# tick-wifi-mk-1_1a.net
KiCad netlist of a schematic drawn in EAGLE
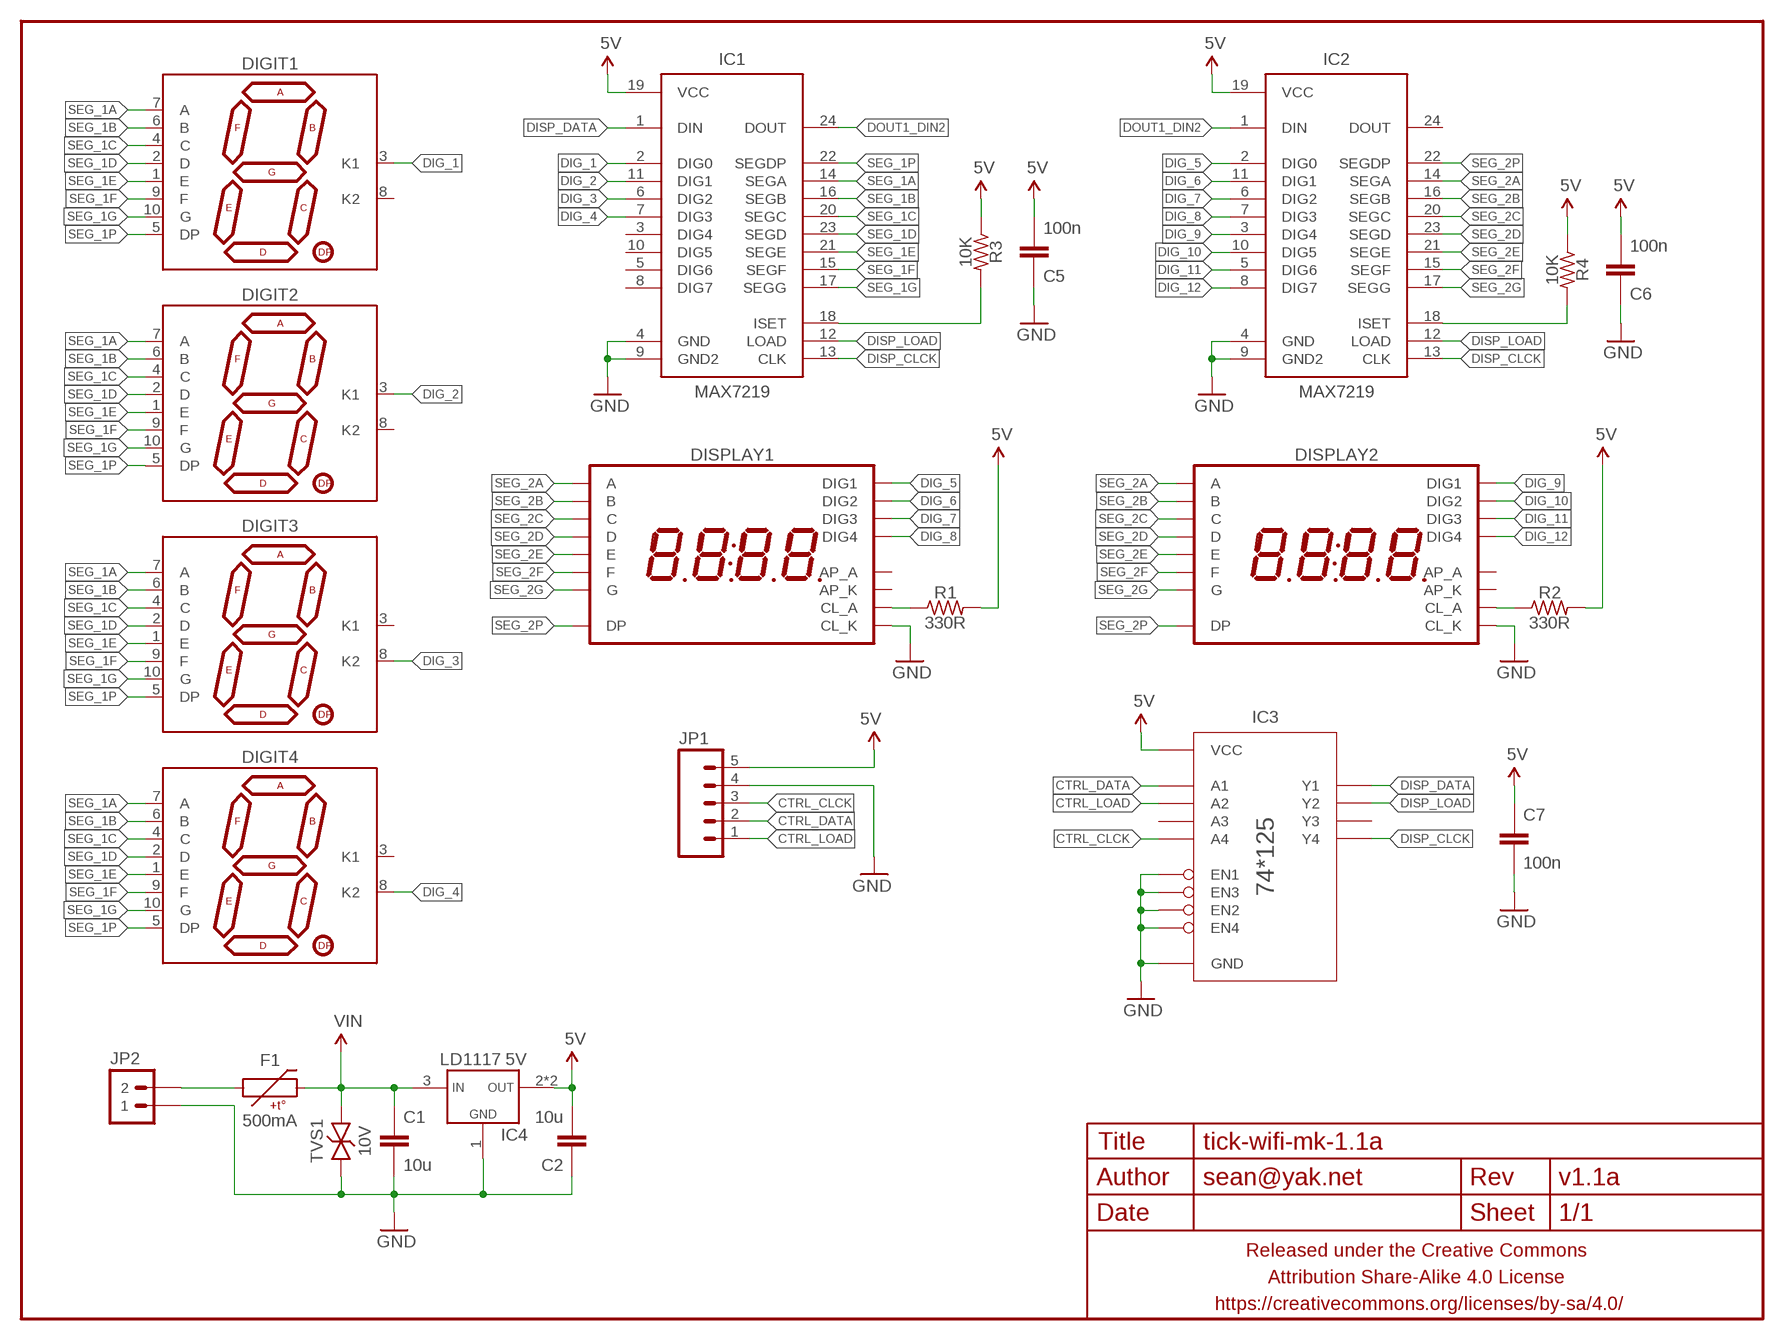
[diagram p0: schematic, sheet 1]

(export (version "E")
  (design (tool "Eeschema 10.0.6"))
  (components
    (comp (ref "C1")
      (value "10u")
      (footprint "eagle-import:C1210")
      (libsource (lib "eagle-import") (part "CAPACITOR-CERAMICC1210"))
    )
    (comp (ref "C2")
      (value "10u")
      (footprint "eagle-import:C1210")
      (libsource (lib "eagle-import") (part "CAPACITOR-CERAMICC1210"))
    )
    (comp (ref "C5")
      (value "100n")
      (footprint "eagle-import:C0603")
      (libsource (lib "eagle-import") (part "CAPACITOR-CERAMICC0603"))
    )
    (comp (ref "C6")
      (value "100n")
      (footprint "eagle-import:C0603")
      (libsource (lib "eagle-import") (part "CAPACITOR-CERAMICC0603"))
    )
    (comp (ref "C7")
      (value "100n")
      (footprint "eagle-import:C0603")
      (libsource (lib "eagle-import") (part "CAPACITOR-CERAMICC0603"))
    )
    (comp (ref "DIGIT1")
      (value "7SEG_1DIGPTH-25.4MM-BARE")
      (footprint "eagle-import:7SEG_1DIG_25.4MM_NOSILK")
      (libsource (lib "eagle-import") (part "7SEG_1DIGPTH-25.4MM-BARE"))
    )
    (comp (ref "DIGIT2")
      (value "7SEG_1DIGPTH-25.4MM-BARE")
      (footprint "eagle-import:7SEG_1DIG_25.4MM_NOSILK")
      (libsource (lib "eagle-import") (part "7SEG_1DIGPTH-25.4MM-BARE"))
    )
    (comp (ref "DIGIT3")
      (value "7SEG_1DIGPTH-25.4MM-BARE")
      (footprint "eagle-import:7SEG_1DIG_25.4MM_NOSILK")
      (libsource (lib "eagle-import") (part "7SEG_1DIGPTH-25.4MM-BARE"))
    )
    (comp (ref "DIGIT4")
      (value "7SEG_1DIGPTH-25.4MM-BARE")
      (footprint "eagle-import:7SEG_1DIG_25.4MM_NOSILK")
      (libsource (lib "eagle-import") (part "7SEG_1DIGPTH-25.4MM-BARE"))
    )
    (comp (ref "DISPLAY1")
      (value "7SEG_4DIGIT_COLON_APOS")
      (footprint "eagle-import:7SEG_4DIG_10MM")
      (libsource (lib "eagle-import") (part "7SEG_4DIGIT_COLON_APOS"))
    )
    (comp (ref "DISPLAY2")
      (value "7SEG_4DIGIT_COLON_APOS")
      (footprint "eagle-import:7SEG_4DIG_10MM")
      (libsource (lib "eagle-import") (part "7SEG_4DIGIT_COLON_APOS"))
    )
    (comp (ref "F1")
      (value "500mA")
      (footprint "eagle-import:PTC-1210")
      (libsource (lib "eagle-import") (part "PTCPTC-1210"))
    )
    (comp (ref "FRAME1")
      (value "FRAME-LETTERNO_PACKAGE")
      (footprint "eagle-import:DUMMY")
      (fields (field (name "DESIGNER") "sean@yak.net") (field (name "VERSION") "v1.1a"))
      (libsource (lib "eagle-import") (part "FRAME-LETTERNO_PACKAGE"))
    )
    (comp (ref "IC1")
      (value "MAX7219")
      (footprint "eagle-import:SO24W")
      (libsource (lib "eagle-import") (part "MAX7219SOIC-W"))
    )
    (comp (ref "IC2")
      (value "MAX7219")
      (footprint "eagle-import:SO24W")
      (libsource (lib "eagle-import") (part "MAX7219SOIC-W"))
    )
    (comp (ref "IC3")
      (value "74HC125")
      (footprint "eagle-import:SO14")
      (libsource (lib "eagle-import") (part "74125SOIC14"))
    )
    (comp (ref "IC4")
      (value "LD1117 5V")
      (footprint "eagle-import:SOT223")
      (libsource (lib "eagle-import") (part "VREG_1117SOT223"))
    )
    (comp (ref "JP1")
      (value "M05PTH-CENTERED")
      (footprint "eagle-import:1X05_PTH_CENTERED")
      (libsource (lib "eagle-import") (part "M05PTH-CENTERED"))
    )
    (comp (ref "JP2")
      (value "M02PTH-CENTERED-R+")
      (footprint "eagle-import:1X02-CENTER-R+")
      (libsource (lib "eagle-import") (part "M02PTH-CENTERED-R+"))
    )
    (comp (ref "R1")
      (value "330R")
      (footprint "eagle-import:R0603")
      (libsource (lib "eagle-import") (part "RESISTORR0603"))
    )
    (comp (ref "R2")
      (value "330R")
      (footprint "eagle-import:R0603")
      (libsource (lib "eagle-import") (part "RESISTORR0603"))
    )
    (comp (ref "R3")
      (value "10K")
      (footprint "eagle-import:R0603")
      (libsource (lib "eagle-import") (part "RESISTORR0603"))
    )
    (comp (ref "R4")
      (value "10K")
      (footprint "eagle-import:R0603")
      (libsource (lib "eagle-import") (part "RESISTORR0603"))
    )
    (comp (ref "TVS1")
      (value "10V")
      (footprint "eagle-import:SMA-DIODE-TVS-BIDIR")
      (libsource (lib "eagle-import") (part "TVSSMA"))
    )
  )
  (nets
    (net (code "1") (name "5V") (class "Default")
      (node (ref "C2") (pin "2") (pinfunction "2_2") (pintype "passive"))
      (node (ref "C5") (pin "2") (pinfunction "2_2") (pintype "passive"))
      (node (ref "C6") (pin "2") (pinfunction "2_2") (pintype "passive"))
      (node (ref "C7") (pin "1") (pinfunction "1_1") (pintype "passive"))
      (node (ref "IC1") (pin "19") (pinfunction "VCC_19") (pintype "bidirectional"))
      (node (ref "IC2") (pin "19") (pinfunction "VCC_19") (pintype "bidirectional"))
      (node (ref "IC3") (pin "14") (pinfunction "VCC_14") (pintype "bidirectional"))
      (node (ref "IC4") (pin "2") (pinfunction "VOUT_2") (pintype "bidirectional"))
      (node (ref "IC4") (pin "4") (pinfunction "VOUT_4") (pintype "bidirectional"))
      (node (ref "JP1") (pin "5") (pinfunction "5_5") (pintype "passive"))
      (node (ref "R1") (pin "2") (pinfunction "2_2") (pintype "passive"))
      (node (ref "R2") (pin "2") (pinfunction "2_2") (pintype "passive"))
      (node (ref "R3") (pin "1") (pinfunction "1_1") (pintype "passive"))
      (node (ref "R4") (pin "1") (pinfunction "1_1") (pintype "passive"))
    )
    (net (code "2") (name "CTRL_CLCK") (class "Default")
      (node (ref "IC3") (pin "12") (pinfunction "A4_12") (pintype "bidirectional"))
      (node (ref "JP1") (pin "3") (pinfunction "3_3") (pintype "passive"))
    )
    (net (code "3") (name "CTRL_DATA") (class "Default")
      (node (ref "IC3") (pin "2") (pinfunction "A1_2") (pintype "bidirectional"))
      (node (ref "JP1") (pin "2") (pinfunction "2_2") (pintype "passive"))
    )
    (net (code "4") (name "CTRL_LOAD") (class "Default")
      (node (ref "IC3") (pin "5") (pinfunction "A2_5") (pintype "bidirectional"))
      (node (ref "JP1") (pin "1") (pinfunction "1_1") (pintype "passive"))
    )
    (net (code "5") (name "DIG_1") (class "Default")
      (node (ref "DIGIT1") (pin "3") (pinfunction "K1_3") (pintype "bidirectional"))
      (node (ref "IC1") (pin "2") (pinfunction "DIG0_2") (pintype "bidirectional"))
    )
    (net (code "6") (name "DIG_2") (class "Default")
      (node (ref "DIGIT2") (pin "3") (pinfunction "K1_3") (pintype "bidirectional"))
      (node (ref "IC1") (pin "11") (pinfunction "DIG1_11") (pintype "bidirectional"))
    )
    (net (code "7") (name "DIG_3") (class "Default")
      (node (ref "DIGIT3") (pin "8") (pinfunction "K2_8") (pintype "bidirectional"))
      (node (ref "IC1") (pin "6") (pinfunction "DIG2_6") (pintype "bidirectional"))
    )
    (net (code "8") (name "DIG_4") (class "Default")
      (node (ref "DIGIT4") (pin "8") (pinfunction "K2_8") (pintype "bidirectional"))
      (node (ref "IC1") (pin "7") (pinfunction "DIG3_7") (pintype "bidirectional"))
    )
    (net (code "9") (name "DIG_5") (class "Default")
      (node (ref "DISPLAY1") (pin "1") (pinfunction "DIG1_1") (pintype "passive"))
      (node (ref "IC2") (pin "2") (pinfunction "DIG0_2") (pintype "bidirectional"))
    )
    (net (code "10") (name "DIG_6") (class "Default")
      (node (ref "DISPLAY1") (pin "2") (pinfunction "DIG2_2") (pintype "passive"))
      (node (ref "IC2") (pin "11") (pinfunction "DIG1_11") (pintype "bidirectional"))
    )
    (net (code "11") (name "DIG_7") (class "Default")
      (node (ref "DISPLAY1") (pin "6") (pinfunction "DIG3_6") (pintype "passive"))
      (node (ref "IC2") (pin "6") (pinfunction "DIG2_6") (pintype "bidirectional"))
    )
    (net (code "12") (name "DIG_8") (class "Default")
      (node (ref "DISPLAY1") (pin "8") (pinfunction "DIG4_8") (pintype "passive"))
      (node (ref "IC2") (pin "7") (pinfunction "DIG3_7") (pintype "bidirectional"))
    )
    (net (code "13") (name "DIG_9") (class "Default")
      (node (ref "DISPLAY2") (pin "1") (pinfunction "DIG1_1") (pintype "passive"))
      (node (ref "IC2") (pin "3") (pinfunction "DIG4_3") (pintype "bidirectional"))
    )
    (net (code "14") (name "DIG_10") (class "Default")
      (node (ref "DISPLAY2") (pin "2") (pinfunction "DIG2_2") (pintype "passive"))
      (node (ref "IC2") (pin "10") (pinfunction "DIG5_10") (pintype "bidirectional"))
    )
    (net (code "15") (name "DIG_11") (class "Default")
      (node (ref "DISPLAY2") (pin "6") (pinfunction "DIG3_6") (pintype "passive"))
      (node (ref "IC2") (pin "5") (pinfunction "DIG6_5") (pintype "bidirectional"))
    )
    (net (code "16") (name "DIG_12") (class "Default")
      (node (ref "DISPLAY2") (pin "8") (pinfunction "DIG4_8") (pintype "passive"))
      (node (ref "IC2") (pin "8") (pinfunction "DIG7_8") (pintype "bidirectional"))
    )
    (net (code "17") (name "DISP_CLCK") (class "Default")
      (node (ref "IC1") (pin "13") (pinfunction "CLK_13") (pintype "bidirectional"))
      (node (ref "IC2") (pin "13") (pinfunction "CLK_13") (pintype "bidirectional"))
      (node (ref "IC3") (pin "11") (pinfunction "Y4_11") (pintype "bidirectional"))
    )
    (net (code "18") (name "DISP_DATA") (class "Default")
      (node (ref "IC1") (pin "1") (pinfunction "DIN_1") (pintype "bidirectional"))
      (node (ref "IC3") (pin "3") (pinfunction "Y1_3") (pintype "bidirectional"))
    )
    (net (code "19") (name "DISP_LOAD") (class "Default")
      (node (ref "IC1") (pin "12") (pinfunction "LOAD_12") (pintype "bidirectional"))
      (node (ref "IC2") (pin "12") (pinfunction "LOAD_12") (pintype "bidirectional"))
      (node (ref "IC3") (pin "6") (pinfunction "Y2_6") (pintype "bidirectional"))
    )
    (net (code "20") (name "DOUT1_DIN2") (class "Default")
      (node (ref "IC1") (pin "24") (pinfunction "DOUT_24") (pintype "bidirectional"))
      (node (ref "IC2") (pin "1") (pinfunction "DIN_1") (pintype "bidirectional"))
    )
    (net (code "21") (name "GND") (class "Default")
      (node (ref "C1") (pin "2") (pinfunction "2_2") (pintype "passive"))
      (node (ref "C2") (pin "1") (pinfunction "1_1") (pintype "passive"))
      (node (ref "C5") (pin "1") (pinfunction "1_1") (pintype "passive"))
      (node (ref "C6") (pin "1") (pinfunction "1_1") (pintype "passive"))
      (node (ref "C7") (pin "2") (pinfunction "2_2") (pintype "passive"))
      (node (ref "DISPLAY1") (pin "12") (pinfunction "CL_K_12") (pintype "passive"))
      (node (ref "DISPLAY2") (pin "12") (pinfunction "CL_K_12") (pintype "passive"))
      (node (ref "IC1") (pin "4") (pinfunction "GND_4") (pintype "bidirectional"))
      (node (ref "IC1") (pin "9") (pinfunction "GND2_9") (pintype "bidirectional"))
      (node (ref "IC2") (pin "4") (pinfunction "GND_4") (pintype "bidirectional"))
      (node (ref "IC2") (pin "9") (pinfunction "GND2_9") (pintype "bidirectional"))
      (node (ref "IC3") (pin "1") (pinfunction "EN1_1") (pintype "bidirectional"))
      (node (ref "IC3") (pin "10") (pinfunction "EN3_10") (pintype "bidirectional"))
      (node (ref "IC3") (pin "13") (pinfunction "EN4_13") (pintype "bidirectional"))
      (node (ref "IC3") (pin "4") (pinfunction "EN2_4") (pintype "bidirectional"))
      (node (ref "IC3") (pin "7") (pinfunction "GND_7") (pintype "bidirectional"))
      (node (ref "IC4") (pin "1") (pinfunction "GND_1") (pintype "bidirectional"))
      (node (ref "JP1") (pin "4") (pinfunction "4_4") (pintype "passive"))
      (node (ref "JP2") (pin "1") (pinfunction "1_1") (pintype "passive"))
      (node (ref "TVS1") (pin "1") (pinfunction "1_1") (pintype "passive"))
    )
    (net (code "22") (name "Net-(DISPLAY1-CL_A)") (class "Default")
      (node (ref "DISPLAY1") (pin "4") (pinfunction "CL_A_4") (pintype "passive"))
      (node (ref "R1") (pin "1") (pinfunction "1_1") (pintype "passive"))
    )
    (net (code "23") (name "Net-(DISPLAY2-CL_A)") (class "Default")
      (node (ref "DISPLAY2") (pin "4") (pinfunction "CL_A_4") (pintype "passive"))
      (node (ref "R2") (pin "1") (pinfunction "1_1") (pintype "passive"))
    )
    (net (code "24") (name "Net-(F1-Pad1)") (class "Default")
      (node (ref "F1") (pin "1") (pinfunction "1_1") (pintype "passive"))
      (node (ref "JP2") (pin "2") (pinfunction "2_2") (pintype "passive"))
    )
    (net (code "25") (name "Net-(IC1-ISET)") (class "Default")
      (node (ref "IC1") (pin "18") (pinfunction "ISET_18") (pintype "bidirectional"))
      (node (ref "R3") (pin "2") (pinfunction "2_2") (pintype "passive"))
    )
    (net (code "26") (name "Net-(IC2-ISET)") (class "Default")
      (node (ref "IC2") (pin "18") (pinfunction "ISET_18") (pintype "bidirectional"))
      (node (ref "R4") (pin "2") (pinfunction "2_2") (pintype "passive"))
    )
    (net (code "27") (name "SEG_1A") (class "Default")
      (node (ref "DIGIT1") (pin "7") (pinfunction "A_7") (pintype "bidirectional"))
      (node (ref "DIGIT2") (pin "7") (pinfunction "A_7") (pintype "bidirectional"))
      (node (ref "DIGIT3") (pin "7") (pinfunction "A_7") (pintype "bidirectional"))
      (node (ref "DIGIT4") (pin "7") (pinfunction "A_7") (pintype "bidirectional"))
      (node (ref "IC1") (pin "14") (pinfunction "SEGA_14") (pintype "bidirectional"))
    )
    (net (code "28") (name "SEG_1B") (class "Default")
      (node (ref "DIGIT1") (pin "6") (pinfunction "B_6") (pintype "bidirectional"))
      (node (ref "DIGIT2") (pin "6") (pinfunction "B_6") (pintype "bidirectional"))
      (node (ref "DIGIT3") (pin "6") (pinfunction "B_6") (pintype "bidirectional"))
      (node (ref "DIGIT4") (pin "6") (pinfunction "B_6") (pintype "bidirectional"))
      (node (ref "IC1") (pin "16") (pinfunction "SEGB_16") (pintype "bidirectional"))
    )
    (net (code "29") (name "SEG_1C") (class "Default")
      (node (ref "DIGIT1") (pin "4") (pinfunction "C_4") (pintype "bidirectional"))
      (node (ref "DIGIT2") (pin "4") (pinfunction "C_4") (pintype "bidirectional"))
      (node (ref "DIGIT3") (pin "4") (pinfunction "C_4") (pintype "bidirectional"))
      (node (ref "DIGIT4") (pin "4") (pinfunction "C_4") (pintype "bidirectional"))
      (node (ref "IC1") (pin "20") (pinfunction "SEGC_20") (pintype "bidirectional"))
    )
    (net (code "30") (name "SEG_1D") (class "Default")
      (node (ref "DIGIT1") (pin "2") (pinfunction "D_2") (pintype "bidirectional"))
      (node (ref "DIGIT2") (pin "2") (pinfunction "D_2") (pintype "bidirectional"))
      (node (ref "DIGIT3") (pin "2") (pinfunction "D_2") (pintype "bidirectional"))
      (node (ref "DIGIT4") (pin "2") (pinfunction "D_2") (pintype "bidirectional"))
      (node (ref "IC1") (pin "23") (pinfunction "SEGD_23") (pintype "bidirectional"))
    )
    (net (code "31") (name "SEG_1E") (class "Default")
      (node (ref "DIGIT1") (pin "1") (pinfunction "E_1") (pintype "bidirectional"))
      (node (ref "DIGIT2") (pin "1") (pinfunction "E_1") (pintype "bidirectional"))
      (node (ref "DIGIT3") (pin "1") (pinfunction "E_1") (pintype "bidirectional"))
      (node (ref "DIGIT4") (pin "1") (pinfunction "E_1") (pintype "bidirectional"))
      (node (ref "IC1") (pin "21") (pinfunction "SEGE_21") (pintype "bidirectional"))
    )
    (net (code "32") (name "SEG_1F") (class "Default")
      (node (ref "DIGIT1") (pin "9") (pinfunction "F_9") (pintype "bidirectional"))
      (node (ref "DIGIT2") (pin "9") (pinfunction "F_9") (pintype "bidirectional"))
      (node (ref "DIGIT3") (pin "9") (pinfunction "F_9") (pintype "bidirectional"))
      (node (ref "DIGIT4") (pin "9") (pinfunction "F_9") (pintype "bidirectional"))
      (node (ref "IC1") (pin "15") (pinfunction "SEGF_15") (pintype "bidirectional"))
    )
    (net (code "33") (name "SEG_1G") (class "Default")
      (node (ref "DIGIT1") (pin "10") (pinfunction "G_10") (pintype "bidirectional"))
      (node (ref "DIGIT2") (pin "10") (pinfunction "G_10") (pintype "bidirectional"))
      (node (ref "DIGIT3") (pin "10") (pinfunction "G_10") (pintype "bidirectional"))
      (node (ref "DIGIT4") (pin "10") (pinfunction "G_10") (pintype "bidirectional"))
      (node (ref "IC1") (pin "17") (pinfunction "SEGG_17") (pintype "bidirectional"))
    )
    (net (code "34") (name "SEG_1P") (class "Default")
      (node (ref "DIGIT1") (pin "5") (pinfunction "DP_5") (pintype "bidirectional"))
      (node (ref "DIGIT2") (pin "5") (pinfunction "DP_5") (pintype "bidirectional"))
      (node (ref "DIGIT3") (pin "5") (pinfunction "DP_5") (pintype "bidirectional"))
      (node (ref "DIGIT4") (pin "5") (pinfunction "DP_5") (pintype "bidirectional"))
      (node (ref "IC1") (pin "22") (pinfunction "SEGDP_22") (pintype "bidirectional"))
    )
    (net (code "35") (name "SEG_2A") (class "Default")
      (node (ref "DISPLAY1") (pin "14") (pinfunction "A_14") (pintype "passive"))
      (node (ref "DISPLAY2") (pin "14") (pinfunction "A_14") (pintype "passive"))
      (node (ref "IC2") (pin "14") (pinfunction "SEGA_14") (pintype "bidirectional"))
    )
    (net (code "36") (name "SEG_2B") (class "Default")
      (node (ref "DISPLAY1") (pin "16") (pinfunction "B_16") (pintype "passive"))
      (node (ref "DISPLAY2") (pin "16") (pinfunction "B_16") (pintype "passive"))
      (node (ref "IC2") (pin "16") (pinfunction "SEGB_16") (pintype "bidirectional"))
    )
    (net (code "37") (name "SEG_2C") (class "Default")
      (node (ref "DISPLAY1") (pin "13") (pinfunction "C_13") (pintype "passive"))
      (node (ref "DISPLAY2") (pin "13") (pinfunction "C_13") (pintype "passive"))
      (node (ref "IC2") (pin "20") (pinfunction "SEGC_20") (pintype "bidirectional"))
    )
    (net (code "38") (name "SEG_2D") (class "Default")
      (node (ref "DISPLAY1") (pin "3") (pinfunction "D_3") (pintype "passive"))
      (node (ref "DISPLAY2") (pin "3") (pinfunction "D_3") (pintype "passive"))
      (node (ref "IC2") (pin "23") (pinfunction "SEGD_23") (pintype "bidirectional"))
    )
    (net (code "39") (name "SEG_2E") (class "Default")
      (node (ref "DISPLAY1") (pin "5") (pinfunction "E_5") (pintype "passive"))
      (node (ref "DISPLAY2") (pin "5") (pinfunction "E_5") (pintype "passive"))
      (node (ref "IC2") (pin "21") (pinfunction "SEGE_21") (pintype "bidirectional"))
    )
    (net (code "40") (name "SEG_2F") (class "Default")
      (node (ref "DISPLAY1") (pin "11") (pinfunction "F_11") (pintype "passive"))
      (node (ref "DISPLAY2") (pin "11") (pinfunction "F_11") (pintype "passive"))
      (node (ref "IC2") (pin "15") (pinfunction "SEGF_15") (pintype "bidirectional"))
    )
    (net (code "41") (name "SEG_2G") (class "Default")
      (node (ref "DISPLAY1") (pin "15") (pinfunction "G_15") (pintype "passive"))
      (node (ref "DISPLAY2") (pin "15") (pinfunction "G_15") (pintype "passive"))
      (node (ref "IC2") (pin "17") (pinfunction "SEGG_17") (pintype "bidirectional"))
    )
    (net (code "42") (name "SEG_2P") (class "Default")
      (node (ref "DISPLAY1") (pin "7") (pinfunction "DP_7") (pintype "passive"))
      (node (ref "DISPLAY2") (pin "7") (pinfunction "DP_7") (pintype "passive"))
      (node (ref "IC2") (pin "22") (pinfunction "SEGDP_22") (pintype "bidirectional"))
    )
    (net (code "43") (name "VIN") (class "Default")
      (node (ref "C1") (pin "1") (pinfunction "1_1") (pintype "passive"))
      (node (ref "F1") (pin "2") (pinfunction "2_2") (pintype "passive"))
      (node (ref "IC4") (pin "3") (pinfunction "VIN_3") (pintype "bidirectional"))
      (node (ref "TVS1") (pin "2") (pinfunction "2_2") (pintype "passive"))
    )
    (net (code "44") (name "unconnected-(DIGIT1-K2-Pad8)") (class "Default")
      (node (ref "DIGIT1") (pin "8") (pinfunction "K2_8") (pintype "bidirectional"))
    )
    (net (code "45") (name "unconnected-(DIGIT2-K2-Pad8)") (class "Default")
      (node (ref "DIGIT2") (pin "8") (pinfunction "K2_8") (pintype "bidirectional"))
    )
    (net (code "46") (name "unconnected-(DIGIT3-K1-Pad3)") (class "Default")
      (node (ref "DIGIT3") (pin "3") (pinfunction "K1_3") (pintype "bidirectional"))
    )
    (net (code "47") (name "unconnected-(DIGIT4-K1-Pad3)") (class "Default")
      (node (ref "DIGIT4") (pin "3") (pinfunction "K1_3") (pintype "bidirectional"))
    )
    (net (code "48") (name "unconnected-(DISPLAY1-AP_A-Pad10)") (class "Default")
      (node (ref "DISPLAY1") (pin "10") (pinfunction "AP_A_10") (pintype "bidirectional"))
    )
    (net (code "49") (name "unconnected-(DISPLAY1-AP_K-Pad9)") (class "Default")
      (node (ref "DISPLAY1") (pin "9") (pinfunction "AP_K_9") (pintype "bidirectional"))
    )
    (net (code "50") (name "unconnected-(DISPLAY2-AP_A-Pad10)") (class "Default")
      (node (ref "DISPLAY2") (pin "10") (pinfunction "AP_A_10") (pintype "bidirectional"))
    )
    (net (code "51") (name "unconnected-(DISPLAY2-AP_K-Pad9)") (class "Default")
      (node (ref "DISPLAY2") (pin "9") (pinfunction "AP_K_9") (pintype "bidirectional"))
    )
    (net (code "52") (name "unconnected-(IC1-DIG4-Pad3)") (class "Default")
      (node (ref "IC1") (pin "3") (pinfunction "DIG4_3") (pintype "bidirectional"))
    )
    (net (code "53") (name "unconnected-(IC1-DIG5-Pad10)") (class "Default")
      (node (ref "IC1") (pin "10") (pinfunction "DIG5_10") (pintype "bidirectional"))
    )
    (net (code "54") (name "unconnected-(IC1-DIG6-Pad5)") (class "Default")
      (node (ref "IC1") (pin "5") (pinfunction "DIG6_5") (pintype "bidirectional"))
    )
    (net (code "55") (name "unconnected-(IC1-DIG7-Pad8)") (class "Default")
      (node (ref "IC1") (pin "8") (pinfunction "DIG7_8") (pintype "bidirectional"))
    )
    (net (code "56") (name "unconnected-(IC2-DOUT-Pad24)") (class "Default")
      (node (ref "IC2") (pin "24") (pinfunction "DOUT_24") (pintype "bidirectional"))
    )
    (net (code "57") (name "unconnected-(IC3-A3-Pad9)") (class "Default")
      (node (ref "IC3") (pin "9") (pinfunction "A3_9") (pintype "bidirectional"))
    )
    (net (code "58") (name "unconnected-(IC3-Y3-Pad8)") (class "Default")
      (node (ref "IC3") (pin "8") (pinfunction "Y3_8") (pintype "bidirectional"))
    )
  )
)
